# IR_module.net
KiCad netlist of a schematic drawn in EAGLE
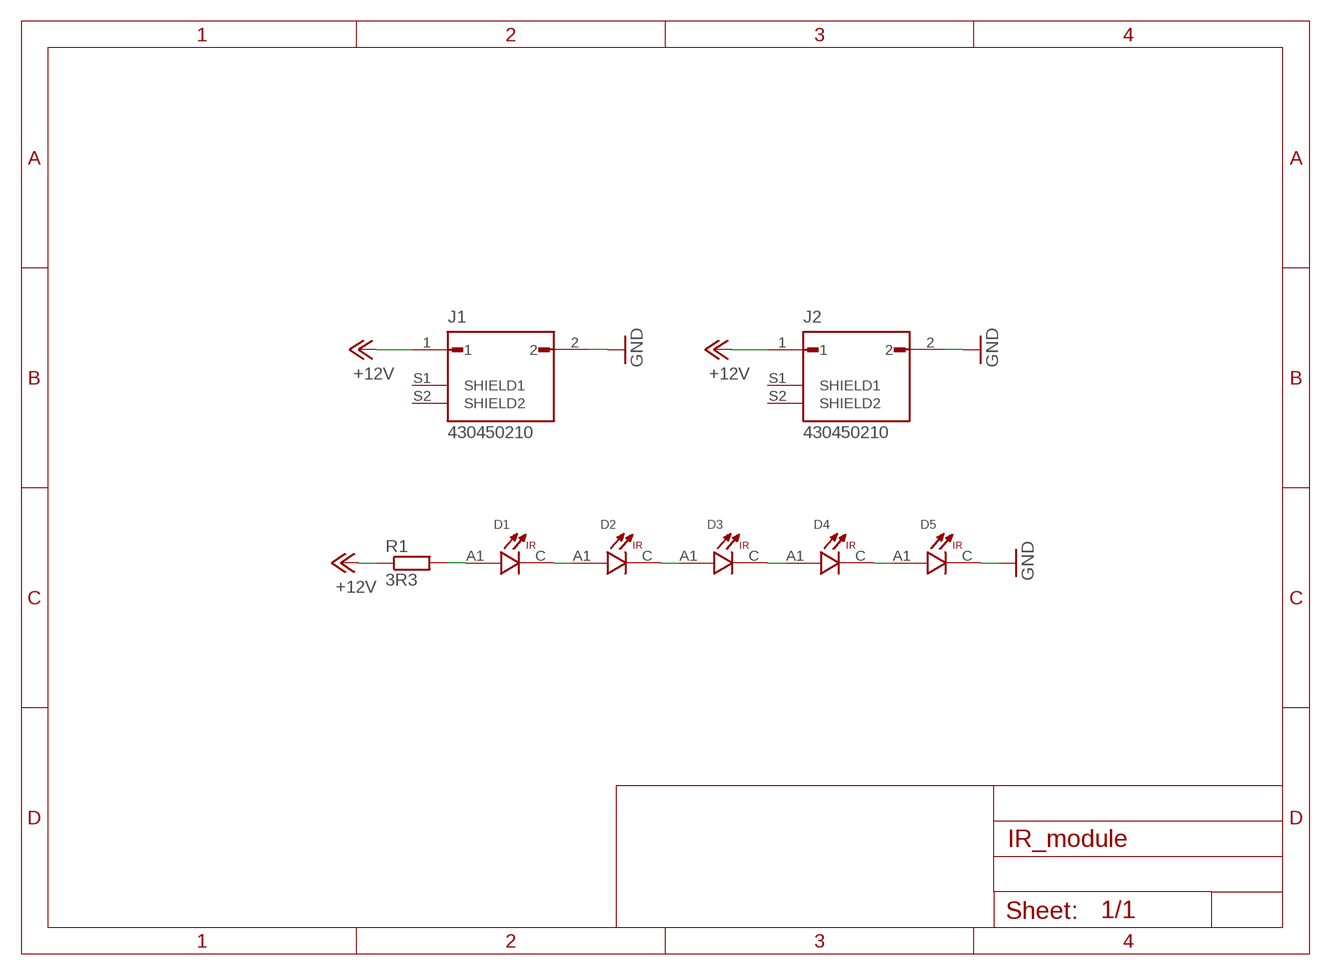
[diagram p0: schematic, sheet 1]

(export (version "E")
  (design (tool "Eeschema 10.0.6"))
  (components
    (comp (ref "D1")
      (value "SFH4716AS")
      (footprint "eagle-import:LED_SFH4716AS")
      (fields (field (name "MF") "OSRAM Opto") (field (name "MP") "SFH 4716AS"))
      (libsource (lib "eagle-import") (part "SFH4716AS"))
    )
    (comp (ref "D2")
      (value "SFH4716AS")
      (footprint "eagle-import:LED_SFH4716AS")
      (fields (field (name "MF") "OSRAM Opto") (field (name "MP") "SFH 4716AS"))
      (libsource (lib "eagle-import") (part "SFH4716AS"))
    )
    (comp (ref "D3")
      (value "SFH4716AS")
      (footprint "eagle-import:LED_SFH4716AS")
      (fields (field (name "MF") "OSRAM Opto") (field (name "MP") "SFH 4716AS"))
      (libsource (lib "eagle-import") (part "SFH4716AS"))
    )
    (comp (ref "D4")
      (value "SFH4716AS")
      (footprint "eagle-import:LED_SFH4716AS")
      (fields (field (name "MF") "OSRAM Opto") (field (name "MP") "SFH 4716AS"))
      (libsource (lib "eagle-import") (part "SFH4716AS"))
    )
    (comp (ref "D5")
      (value "SFH4716AS")
      (footprint "eagle-import:LED_SFH4716AS")
      (fields (field (name "MF") "OSRAM Opto") (field (name "MP") "SFH 4716AS"))
      (libsource (lib "eagle-import") (part "SFH4716AS"))
    )
    (comp (ref "J1")
      (value "430450210")
      (footprint "eagle-import:MOLEX_430450210")
      (fields (field (name "MF") "Molex") (field (name "MP") "43045-0210"))
      (libsource (lib "eagle-import") (part "430450210"))
    )
    (comp (ref "J2")
      (value "430450210")
      (footprint "eagle-import:MOLEX_430450210")
      (fields (field (name "MF") "Molex") (field (name "MP") "43045-0210"))
      (libsource (lib "eagle-import") (part "430450210"))
    )
    (comp (ref "R1")
      (value "3R3")
      (footprint "eagle-import:R2512")
      (libsource (lib "eagle-import") (part "R-EU_R2512"))
    )
  )
  (nets
    (net (code "1") (name "+12V") (class "Default")
      (node (ref "J1") (pin "1") (pinfunction "1_1") (pintype "passive"))
      (node (ref "J2") (pin "1") (pinfunction "1_1") (pintype "passive"))
      (node (ref "R1") (pin "1") (pinfunction "1_1") (pintype "passive"))
    )
    (net (code "2") (name "GND") (class "Default")
      (node (ref "D5") (pin "C") (pinfunction "C_C") (pintype "passive"))
      (node (ref "J1") (pin "2") (pinfunction "2_2") (pintype "passive"))
      (node (ref "J2") (pin "2") (pinfunction "2_2") (pintype "passive"))
    )
    (net (code "3") (name "Net-(D1-A)") (class "Default")
      (node (ref "D1") (pin "A1") (pinfunction "A_A1") (pintype "passive"))
      (node (ref "R1") (pin "2") (pinfunction "2_2") (pintype "passive"))
    )
    (net (code "4") (name "Net-(D2-A)") (class "Default")
      (node (ref "D1") (pin "C") (pinfunction "C_C") (pintype "passive"))
      (node (ref "D2") (pin "A1") (pinfunction "A_A1") (pintype "passive"))
    )
    (net (code "5") (name "Net-(D3-A)") (class "Default")
      (node (ref "D2") (pin "C") (pinfunction "C_C") (pintype "passive"))
      (node (ref "D3") (pin "A1") (pinfunction "A_A1") (pintype "passive"))
    )
    (net (code "6") (name "Net-(D4-A)") (class "Default")
      (node (ref "D3") (pin "C") (pinfunction "C_C") (pintype "passive"))
      (node (ref "D4") (pin "A1") (pinfunction "A_A1") (pintype "passive"))
    )
    (net (code "7") (name "Net-(D5-A)") (class "Default")
      (node (ref "D4") (pin "C") (pinfunction "C_C") (pintype "passive"))
      (node (ref "D5") (pin "A1") (pinfunction "A_A1") (pintype "passive"))
    )
    (net (code "8") (name "unconnected-(J1-SHIELD1-PadS1)") (class "Default")
      (node (ref "J1") (pin "S1") (pinfunction "SHIELD1_S1") (pintype "passive"))
    )
    (net (code "9") (name "unconnected-(J1-SHIELD2-PadS2)") (class "Default")
      (node (ref "J1") (pin "S2") (pinfunction "SHIELD2_S2") (pintype "passive"))
    )
    (net (code "10") (name "unconnected-(J2-SHIELD1-PadS1)") (class "Default")
      (node (ref "J2") (pin "S1") (pinfunction "SHIELD1_S1") (pintype "passive"))
    )
    (net (code "11") (name "unconnected-(J2-SHIELD2-PadS2)") (class "Default")
      (node (ref "J2") (pin "S2") (pinfunction "SHIELD2_S2") (pintype "passive"))
    )
  )
)
